# ATtiny84LEDELSMT.net
KiCad netlist of a schematic drawn in EAGLE
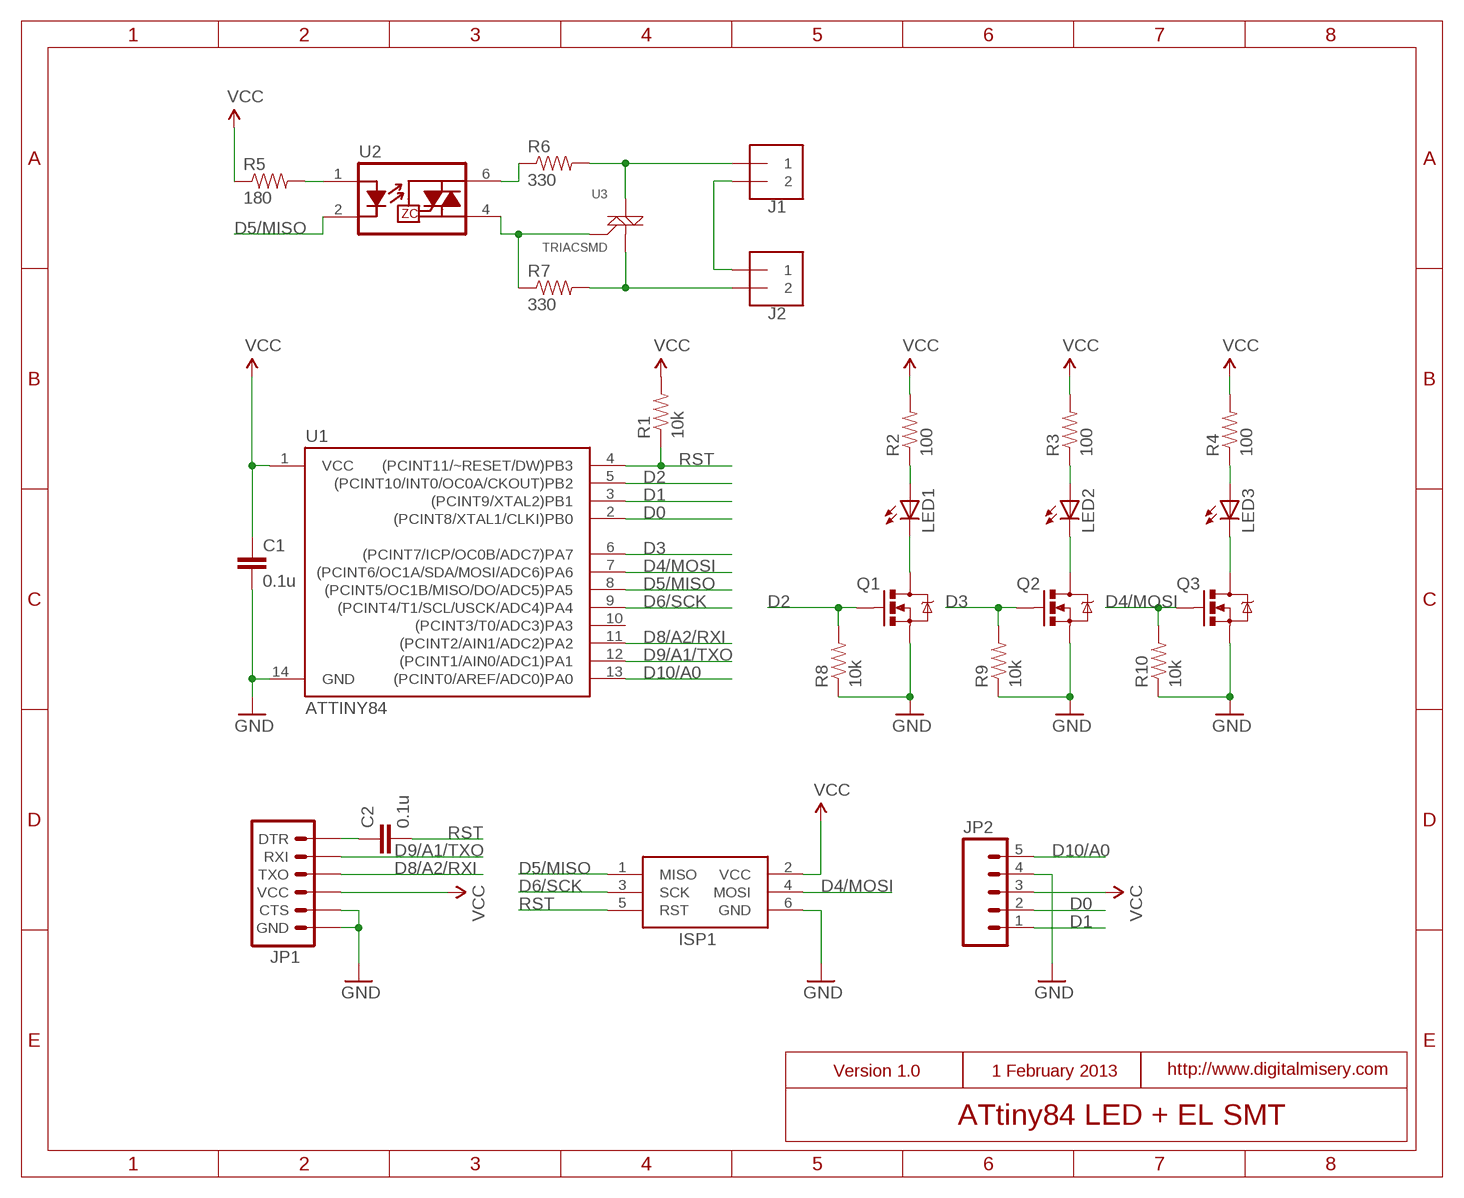
[diagram p0: schematic, sheet 1]

(export (version "E")
  (design (tool "Eeschema 10.0.6"))
  (components
    (comp (ref "C1")
      (value "0.1u")
      (footprint "eagle-import:0805")
      (libsource (lib "eagle-import") (part "CAP0805"))
    )
    (comp (ref "C2")
      (value "0.1u")
      (footprint "eagle-import:0805")
      (libsource (lib "eagle-import") (part "CAP0805"))
    )
    (comp (ref "ISP1")
      (value "AVRISP-6")
      (footprint "eagle-import:AVRISP")
      (libsource (lib "eagle-import") (part "AVRISP-6"))
    )
    (comp (ref "J1")
      (value "1X2-3.5MM")
      (footprint "eagle-import:1X2-3.5MM")
      (libsource (lib "eagle-import") (part "1X2-3.5MM"))
    )
    (comp (ref "J2")
      (value "1X2-3.5MM")
      (footprint "eagle-import:1X2-3.5MM")
      (libsource (lib "eagle-import") (part "1X2-3.5MM"))
    )
    (comp (ref "JP1")
      (value "ARDUINO_SERIAL_PROGRAMPTH")
      (footprint "eagle-import:1X06")
      (libsource (lib "eagle-import") (part "ARDUINO_SERIAL_PROGRAMPTH"))
    )
    (comp (ref "JP2")
      (value "M05PTH")
      (footprint "eagle-import:1X05")
      (libsource (lib "eagle-import") (part "M05PTH"))
    )
    (comp (ref "LED1")
      (value "LED5MM")
      (footprint "eagle-import:LED5MM")
      (libsource (lib "eagle-import") (part "LED5MM"))
    )
    (comp (ref "LED2")
      (value "LED5MM")
      (footprint "eagle-import:LED5MM")
      (libsource (lib "eagle-import") (part "LED5MM"))
    )
    (comp (ref "LED3")
      (value "LED5MM")
      (footprint "eagle-import:LED5MM")
      (libsource (lib "eagle-import") (part "LED5MM"))
    )
    (comp (ref "Q1")
      (value "MOSFET-NCHANNELBSS138")
      (footprint "eagle-import:SOT23")
      (libsource (lib "eagle-import") (part "MOSFET-NCHANNELBSS138"))
    )
    (comp (ref "Q2")
      (value "MOSFET-NCHANNELBSS138")
      (footprint "eagle-import:SOT23")
      (libsource (lib "eagle-import") (part "MOSFET-NCHANNELBSS138"))
    )
    (comp (ref "Q3")
      (value "MOSFET-NCHANNELBSS138")
      (footprint "eagle-import:SOT23")
      (libsource (lib "eagle-import") (part "MOSFET-NCHANNELBSS138"))
    )
    (comp (ref "R1")
      (value "10k")
      (footprint "eagle-import:0805")
      (libsource (lib "eagle-import") (part "RESISTOR0805-RES"))
    )
    (comp (ref "R2")
      (value "100")
      (footprint "eagle-import:0805")
      (libsource (lib "eagle-import") (part "RESISTOR0805-RES"))
    )
    (comp (ref "R3")
      (value "100")
      (footprint "eagle-import:0805")
      (libsource (lib "eagle-import") (part "RESISTOR0805-RES"))
    )
    (comp (ref "R4")
      (value "100")
      (footprint "eagle-import:0805")
      (libsource (lib "eagle-import") (part "RESISTOR0805-RES"))
    )
    (comp (ref "R5")
      (value "180")
      (footprint "eagle-import:0805")
      (libsource (lib "eagle-import") (part "RESISTOR0805-RES"))
    )
    (comp (ref "R6")
      (value "330")
      (footprint "eagle-import:0805")
      (libsource (lib "eagle-import") (part "RESISTOR0805-RES"))
    )
    (comp (ref "R7")
      (value "330")
      (footprint "eagle-import:0805")
      (libsource (lib "eagle-import") (part "RESISTOR0805-RES"))
    )
    (comp (ref "R8")
      (value "10k")
      (footprint "eagle-import:0805")
      (libsource (lib "eagle-import") (part "RESISTOR0805-RES"))
    )
    (comp (ref "R9")
      (value "10k")
      (footprint "eagle-import:0805")
      (libsource (lib "eagle-import") (part "RESISTOR0805-RES"))
    )
    (comp (ref "R10")
      (value "10k")
      (footprint "eagle-import:0805")
      (libsource (lib "eagle-import") (part "RESISTOR0805-RES"))
    )
    (comp (ref "U1")
      (value "ATTINY84")
      (footprint "eagle-import:SO14")
      (libsource (lib "eagle-import") (part "ATTINY84"))
    )
    (comp (ref "U2")
      (value "MOC3063S")
      (footprint "eagle-import:DIP8SMD")
      (libsource (lib "eagle-import") (part "MOC3063S"))
    )
    (comp (ref "U3")
      (value "TRIACSMD")
      (footprint "eagle-import:SOT223")
      (libsource (lib "eagle-import") (part "TRIACSMD"))
    )
  )
  (nets
    (net (code "1") (name "/D0") (class "Default")
      (node (ref "JP2") (pin "2") (pinfunction "2_2") (pintype "passive"))
      (node (ref "U1") (pin "2") (pinfunction "(PCINT8/XTAL1/CLKI)PB0_2") (pintype "bidirectional"))
    )
    (net (code "2") (name "/D1") (class "Default")
      (node (ref "JP2") (pin "1") (pinfunction "1_1") (pintype "passive"))
      (node (ref "U1") (pin "3") (pinfunction "(PCINT9/XTAL2)PB1_3") (pintype "bidirectional"))
    )
    (net (code "3") (name "/D2") (class "Default")
      (node (ref "Q1") (pin "1") (pinfunction "G_1") (pintype "passive"))
      (node (ref "R8") (pin "2") (pinfunction "2_2") (pintype "passive"))
      (node (ref "U1") (pin "5") (pinfunction "(PCINT10/INT0/OC0A/CKOUT)PB2_5") (pintype "bidirectional"))
    )
    (net (code "4") (name "/D3") (class "Default")
      (node (ref "Q2") (pin "1") (pinfunction "G_1") (pintype "passive"))
      (node (ref "R9") (pin "2") (pinfunction "2_2") (pintype "passive"))
      (node (ref "U1") (pin "6") (pinfunction "(PCINT7/ICP/OC0B/ADC7)PA7_6") (pintype "bidirectional"))
    )
    (net (code "5") (name "/D4{slash}MOSI") (class "Default")
      (node (ref "ISP1") (pin "4") (pinfunction "MOSI_4") (pintype "output"))
      (node (ref "Q3") (pin "1") (pinfunction "G_1") (pintype "passive"))
      (node (ref "R10") (pin "2") (pinfunction "2_2") (pintype "passive"))
      (node (ref "U1") (pin "7") (pinfunction "(PCINT6/OC1A/SDA/MOSI/ADC6)PA6_7") (pintype "bidirectional"))
    )
    (net (code "6") (name "/D5{slash}MISO") (class "Default")
      (node (ref "ISP1") (pin "1") (pinfunction "MISO_1") (pintype "input"))
      (node (ref "U1") (pin "8") (pinfunction "(PCINT5/OC1B/MISO/DO/ADC5)PA5_8") (pintype "bidirectional"))
      (node (ref "U2") (pin "2") (pinfunction "K_2") (pintype "bidirectional"))
    )
    (net (code "7") (name "/D6{slash}SCK") (class "Default")
      (node (ref "ISP1") (pin "3") (pinfunction "SCK_3") (pintype "output"))
      (node (ref "U1") (pin "9") (pinfunction "(PCINT4/T1/SCL/USCK/ADC4)PA4_9") (pintype "bidirectional"))
    )
    (net (code "8") (name "/D8{slash}A2{slash}RXI") (class "Default")
      (node (ref "JP1") (pin "3") (pinfunction "TXO_3") (pintype "passive"))
      (node (ref "U1") (pin "11") (pinfunction "(PCINT2/AIN1/ADC2)PA2_11") (pintype "bidirectional"))
    )
    (net (code "9") (name "/D9{slash}A1{slash}TXO") (class "Default")
      (node (ref "JP1") (pin "2") (pinfunction "RXI_2") (pintype "passive"))
      (node (ref "U1") (pin "12") (pinfunction "(PCINT1/AIN0/ADC1)PA1_12") (pintype "bidirectional"))
    )
    (net (code "10") (name "/D10{slash}A0") (class "Default")
      (node (ref "JP2") (pin "5") (pinfunction "5_5") (pintype "passive"))
      (node (ref "U1") (pin "13") (pinfunction "(PCINT0/AREF/ADC0)PA0_13") (pintype "bidirectional"))
    )
    (net (code "11") (name "/RST") (class "Default")
      (node (ref "C2") (pin "2") (pinfunction "2_2") (pintype "passive"))
      (node (ref "ISP1") (pin "5") (pinfunction "RST_5") (pintype "output"))
      (node (ref "R1") (pin "1") (pinfunction "1_1") (pintype "passive"))
      (node (ref "U1") (pin "4") (pinfunction "(PCINT11/~{RESET/DW})PB3_4") (pintype "bidirectional"))
    )
    (net (code "12") (name "GND") (class "Default")
      (node (ref "C1") (pin "2") (pinfunction "2_2") (pintype "passive"))
      (node (ref "ISP1") (pin "6") (pinfunction "GND_6") (pintype "power_in"))
      (node (ref "JP1") (pin "5") (pinfunction "CTS_5") (pintype "passive"))
      (node (ref "JP1") (pin "6") (pinfunction "GND_6") (pintype "passive"))
      (node (ref "JP2") (pin "4") (pinfunction "4_4") (pintype "passive"))
      (node (ref "Q1") (pin "2") (pinfunction "S_2") (pintype "passive"))
      (node (ref "Q2") (pin "2") (pinfunction "S_2") (pintype "passive"))
      (node (ref "Q3") (pin "2") (pinfunction "S_2") (pintype "passive"))
      (node (ref "R10") (pin "1") (pinfunction "1_1") (pintype "passive"))
      (node (ref "R8") (pin "1") (pinfunction "1_1") (pintype "passive"))
      (node (ref "R9") (pin "1") (pinfunction "1_1") (pintype "passive"))
      (node (ref "U1") (pin "14") (pinfunction "GND_14") (pintype "bidirectional"))
    )
    (net (code "13") (name "Net-(J1-Pad2)") (class "Default")
      (node (ref "J1") (pin "2") (pinfunction "2_2") (pintype "passive"))
      (node (ref "J2") (pin "1") (pinfunction "1_1") (pintype "passive"))
    )
    (net (code "14") (name "Net-(JP1-DTR)") (class "Default")
      (node (ref "C2") (pin "1") (pinfunction "1_1") (pintype "passive"))
      (node (ref "JP1") (pin "1") (pinfunction "DTR_1") (pintype "passive"))
    )
    (net (code "15") (name "Net-(LED1-C)") (class "Default")
      (node (ref "LED1") (pin "K") (pinfunction "C_K") (pintype "passive"))
      (node (ref "Q1") (pin "3") (pinfunction "D_3") (pintype "passive"))
    )
    (net (code "16") (name "Net-(LED1-PadA)") (class "Default")
      (node (ref "LED1") (pin "A") (pinfunction "A_A") (pintype "passive"))
      (node (ref "R2") (pin "1") (pinfunction "1_1") (pintype "passive"))
    )
    (net (code "17") (name "Net-(LED2-C)") (class "Default")
      (node (ref "LED2") (pin "K") (pinfunction "C_K") (pintype "passive"))
      (node (ref "Q2") (pin "3") (pinfunction "D_3") (pintype "passive"))
    )
    (net (code "18") (name "Net-(LED2-PadA)") (class "Default")
      (node (ref "LED2") (pin "A") (pinfunction "A_A") (pintype "passive"))
      (node (ref "R3") (pin "1") (pinfunction "1_1") (pintype "passive"))
    )
    (net (code "19") (name "Net-(LED3-C)") (class "Default")
      (node (ref "LED3") (pin "K") (pinfunction "C_K") (pintype "passive"))
      (node (ref "Q3") (pin "3") (pinfunction "D_3") (pintype "passive"))
    )
    (net (code "20") (name "Net-(LED3-PadA)") (class "Default")
      (node (ref "LED3") (pin "A") (pinfunction "A_A") (pintype "passive"))
      (node (ref "R4") (pin "1") (pinfunction "1_1") (pintype "passive"))
    )
    (net (code "21") (name "Net-(U2-A)") (class "Default")
      (node (ref "R5") (pin "2") (pinfunction "2_2") (pintype "passive"))
      (node (ref "U2") (pin "1") (pinfunction "A_1") (pintype "bidirectional"))
    )
    (net (code "22") (name "Net-(U2-T1)") (class "Default")
      (node (ref "R6") (pin "1") (pinfunction "1_1") (pintype "passive"))
      (node (ref "U2") (pin "6") (pinfunction "T1_6") (pintype "bidirectional"))
    )
    (net (code "23") (name "Net-(U2-T2)") (class "Default")
      (node (ref "R7") (pin "1") (pinfunction "1_1") (pintype "passive"))
      (node (ref "U2") (pin "4") (pinfunction "T2_4") (pintype "bidirectional"))
      (node (ref "U3") (pin "3") (pinfunction "G_3") (pintype "bidirectional"))
    )
    (net (code "24") (name "Net-(U3-M1)") (class "Default")
      (node (ref "J2") (pin "2") (pinfunction "2_2") (pintype "passive"))
      (node (ref "R7") (pin "2") (pinfunction "2_2") (pintype "passive"))
      (node (ref "U3") (pin "1") (pinfunction "M1_1") (pintype "bidirectional"))
    )
    (net (code "25") (name "Net-(U3-M2)") (class "Default")
      (node (ref "J1") (pin "1") (pinfunction "1_1") (pintype "passive"))
      (node (ref "R6") (pin "2") (pinfunction "2_2") (pintype "passive"))
      (node (ref "U3") (pin "2") (pinfunction "M2_2") (pintype "bidirectional"))
    )
    (net (code "26") (name "VCC") (class "Default")
      (node (ref "C1") (pin "1") (pinfunction "1_1") (pintype "passive"))
      (node (ref "ISP1") (pin "2") (pinfunction "VCC_2") (pintype "power_in"))
      (node (ref "JP1") (pin "4") (pinfunction "VCC_4") (pintype "passive"))
      (node (ref "JP2") (pin "3") (pinfunction "3_3") (pintype "passive"))
      (node (ref "R1") (pin "2") (pinfunction "2_2") (pintype "passive"))
      (node (ref "R2") (pin "2") (pinfunction "2_2") (pintype "passive"))
      (node (ref "R3") (pin "2") (pinfunction "2_2") (pintype "passive"))
      (node (ref "R4") (pin "2") (pinfunction "2_2") (pintype "passive"))
      (node (ref "R5") (pin "1") (pinfunction "1_1") (pintype "passive"))
      (node (ref "U1") (pin "1") (pinfunction "VCC_1") (pintype "bidirectional"))
    )
    (net (code "27") (name "unconnected-(U1-(PCINT3{slash}T0{slash}ADC3)PA3-Pad10)") (class "Default")
      (node (ref "U1") (pin "10") (pinfunction "(PCINT3/T0/ADC3)PA3_10") (pintype "bidirectional"))
    )
  )
)
